# adc1.net
KiCad netlist of a schematic drawn in Altium Designer
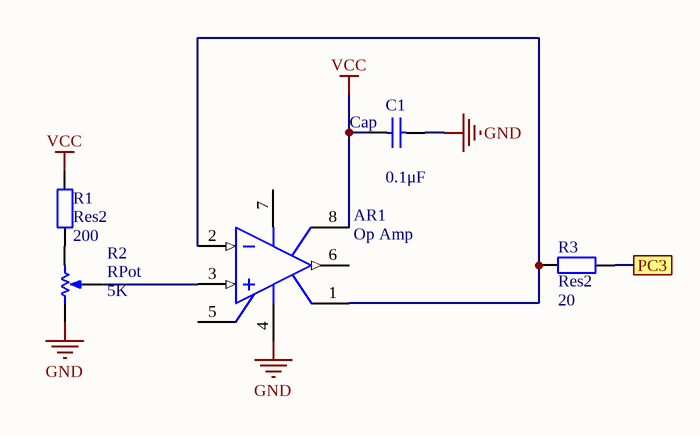
[diagram p0: adc1.SchDoc]

(export (version "E")
  (design (tool "Eeschema 10.0.6"))
  (components
    (comp (ref "AR1")
      (value "Op Amp")
      (footprint "H-08A")
      (description "FET Operational Amplifier")
      (fields (field (name "PUBLISHER") "Altium Limited"))
      (libsource (lib "Miscellaneous Devices") (part "Op Amp"))
    )
    (comp (ref "C1")
      (value "Cap")
      (footprint "RAD-0.3")
      (description "Capacitor")
      (fields (field (name "ALTIUM_VALUE") "0.1μF") (field (name "PUBLISHER") "Altium Limited"))
      (libsource (lib "Miscellaneous Devices") (part "Cap"))
    )
    (comp (ref "R1")
      (value "Res2")
      (footprint "AXIAL-0.4")
      (description "Resistor")
      (fields (field (name "ALTIUM_VALUE") "200") (field (name "PUBLISHER") "Altium Limited"))
      (libsource (lib "Miscellaneous Devices") (part "Res2"))
    )
    (comp (ref "R2")
      (value "RPot")
      (footprint "VR5")
      (description "Potentiometer")
      (fields (field (name "ALTIUM_VALUE") "5K") (field (name "PUBLISHER") "Altium Limited"))
      (libsource (lib "Miscellaneous Devices") (part "RPot"))
    )
    (comp (ref "R3")
      (value "Res2")
      (footprint "AXIAL-0.4")
      (description "Resistor")
      (fields (field (name "ALTIUM_VALUE") "20") (field (name "PUBLISHER") "Altium Limited"))
      (libsource (lib "") (part "Res2_1"))
    )
  )
  (nets
    (net (code "1") (name "/PC3") (class "Default")
      (node (ref "R3") (pin "2") (pinfunction "2_2") (pintype "passive"))
    )
    (net (code "2") (name "GND") (class "Default")
      (node (ref "AR1") (pin "4") (pinfunction "V-_4") (pintype "power_in"))
      (node (ref "C1") (pin "2") (pinfunction "2_2") (pintype "passive"))
      (node (ref "R2") (pin "1") (pinfunction "TOP_1") (pintype "passive"))
    )
    (net (code "3") (name "Net-(AR1-IN+)") (class "Default")
      (node (ref "AR1") (pin "3") (pinfunction "IN+_3") (pintype "input"))
      (node (ref "R2") (pin "3") (pinfunction "TAP_3") (pintype "passive"))
    )
    (net (code "4") (name "Net-(AR1-IN-)") (class "Default")
      (node (ref "AR1") (pin "1") (pinfunction "OS_NUL_1") (pintype "passive"))
      (node (ref "AR1") (pin "2") (pinfunction "IN-_2") (pintype "input"))
      (node (ref "R3") (pin "1") (pinfunction "1_1") (pintype "passive"))
    )
    (net (code "5") (name "Net-(R2-BOT)") (class "Default")
      (node (ref "R1") (pin "1") (pinfunction "1_1") (pintype "passive"))
      (node (ref "R2") (pin "2") (pinfunction "BOT_2") (pintype "passive"))
    )
    (net (code "6") (name "VCC") (class "Default")
      (node (ref "AR1") (pin "8") (pinfunction "TAB_8") (pintype "passive"))
      (node (ref "C1") (pin "1") (pinfunction "1_1") (pintype "passive"))
      (node (ref "R1") (pin "2") (pinfunction "2_2") (pintype "passive"))
    )
    (net (code "7") (name "unconnected-(AR1-OS_NUL-Pad5)") (class "Default")
      (node (ref "AR1") (pin "5") (pinfunction "OS_NUL_5") (pintype "passive"))
    )
    (net (code "8") (name "unconnected-(AR1-OUT-Pad6)") (class "Default")
      (node (ref "AR1") (pin "6") (pinfunction "OUT_6") (pintype "output"))
    )
    (net (code "9") (name "unconnected-(AR1-V+-Pad7)") (class "Default")
      (node (ref "AR1") (pin "7") (pinfunction "V+_7") (pintype "power_in"))
    )
  )
)
